# board_sch.net
KiCad netlist of a schematic drawn in EAGLE
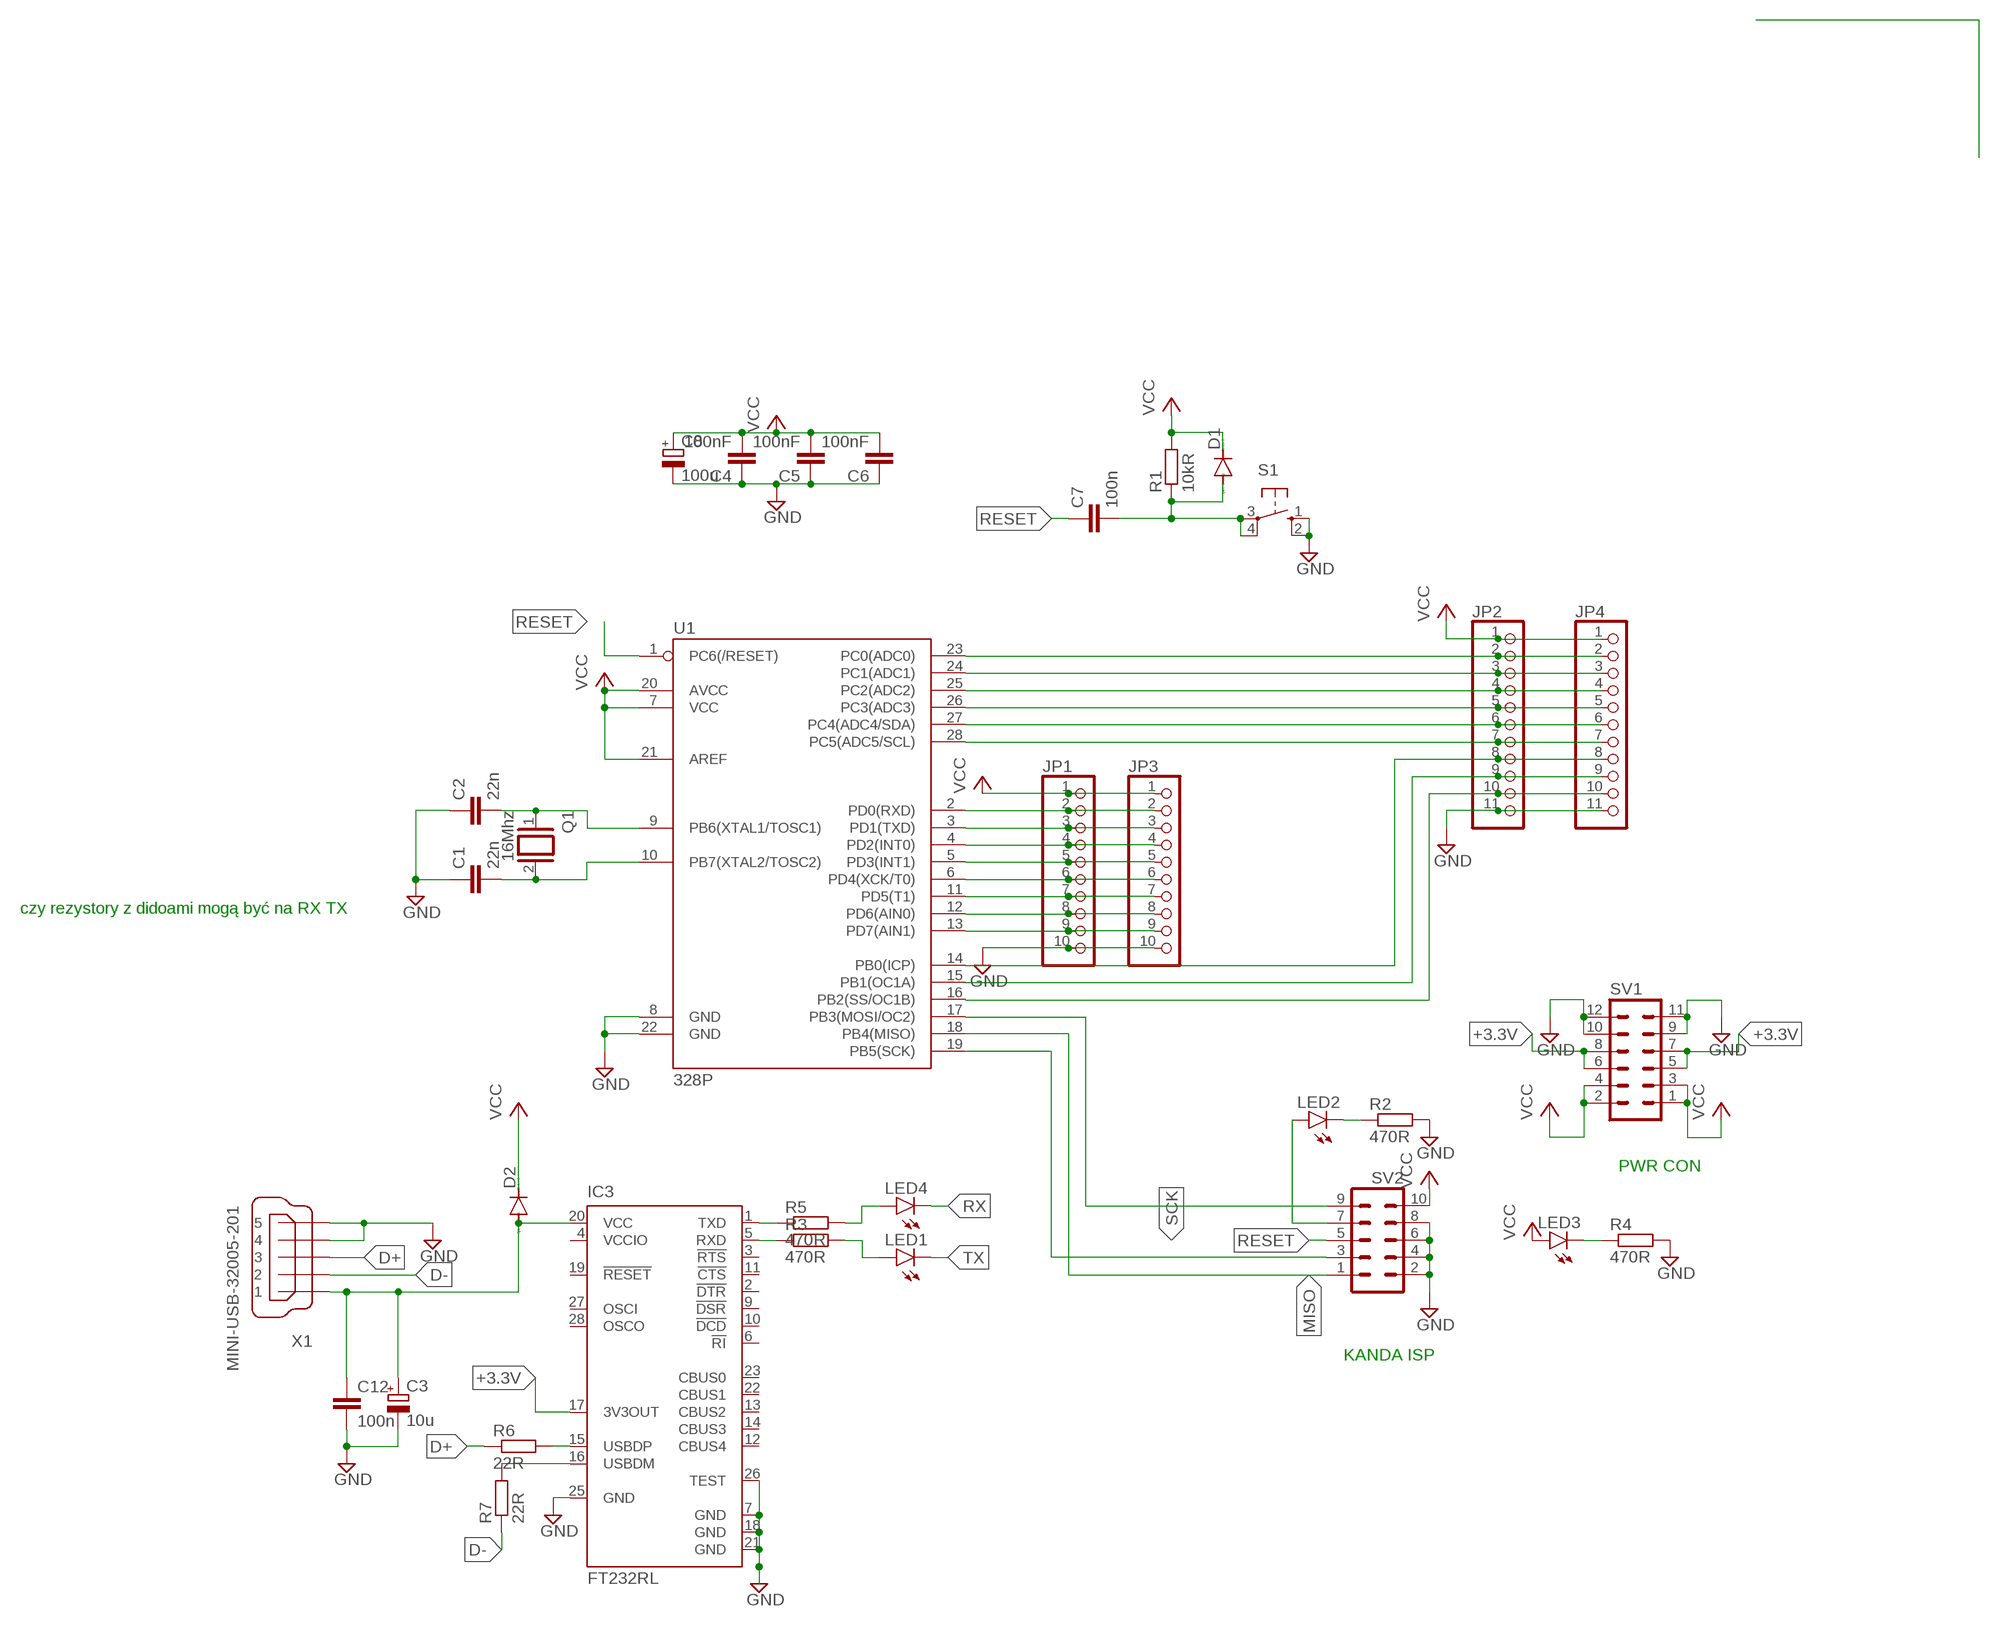
[diagram p0: schematic, sheet 1]

(export (version "E")
  (design (tool "Eeschema 10.0.6"))
  (components
    (comp (ref "C1")
      (value "22n")
      (footprint "eagle-import:C0805")
      (libsource (lib "eagle-import") (part "C-EUC0805"))
    )
    (comp (ref "C2")
      (value "22n")
      (footprint "eagle-import:C0805")
      (libsource (lib "eagle-import") (part "C-EUC0805"))
    )
    (comp (ref "C3")
      (value "10u")
      (footprint "eagle-import:E2,5-6E")
      (libsource (lib "eagle-import") (part "CPOL-EUE2,5-6E"))
    )
    (comp (ref "C4")
      (value "100nF")
      (footprint "eagle-import:C050-025X075")
      (libsource (lib "eagle-import") (part "C-EU050-025X075"))
    )
    (comp (ref "C5")
      (value "100nF")
      (footprint "eagle-import:C050-025X075")
      (libsource (lib "eagle-import") (part "C-EU050-025X075"))
    )
    (comp (ref "C6")
      (value "100nF")
      (footprint "eagle-import:C050-025X075")
      (libsource (lib "eagle-import") (part "C-EU050-025X075"))
    )
    (comp (ref "C7")
      (value "100n")
      (footprint "eagle-import:C0805")
      (libsource (lib "eagle-import") (part "C-EUC0805"))
    )
    (comp (ref "C8")
      (value "100u")
      (footprint "eagle-import:E2,5-6E")
      (libsource (lib "eagle-import") (part "CPOL-EUE2,5-6E"))
    )
    (comp (ref "C12")
      (value "100n")
      (footprint "eagle-import:C0805")
      (libsource (lib "eagle-import") (part "C-EUC0805"))
    )
    (comp (ref "D1")
      (value "DIODE-DO214AC")
      (footprint "eagle-import:DO214AC")
      (libsource (lib "eagle-import") (part "DIODE-DO214AC"))
    )
    (comp (ref "D2")
      (value "DIODE-DO214AC")
      (footprint "eagle-import:DO214AC")
      (libsource (lib "eagle-import") (part "DIODE-DO214AC"))
    )
    (comp (ref "IC3")
      (value "FT232RL")
      (footprint "eagle-import:SSOP28")
      (libsource (lib "eagle-import") (part "FT232RL"))
    )
    (comp (ref "JP1")
      (value "PINHD-1X10")
      (footprint "eagle-import:1X10")
      (libsource (lib "eagle-import") (part "PINHD-1X10"))
    )
    (comp (ref "JP2")
      (value "PINHD-1X11")
      (footprint "eagle-import:1X11")
      (libsource (lib "eagle-import") (part "PINHD-1X11"))
    )
    (comp (ref "JP3")
      (value "PINHD-1X10")
      (footprint "eagle-import:1X10")
      (libsource (lib "eagle-import") (part "PINHD-1X10"))
    )
    (comp (ref "JP4")
      (value "PINHD-1X11")
      (footprint "eagle-import:1X11")
      (libsource (lib "eagle-import") (part "PINHD-1X11"))
    )
    (comp (ref "LED1")
      (value "LEDCHIPLED_0805")
      (footprint "eagle-import:CHIPLED_0805")
      (libsource (lib "eagle-import") (part "LEDCHIPLED_0805"))
    )
    (comp (ref "LED2")
      (value "LEDCHIPLED_0805")
      (footprint "eagle-import:CHIPLED_0805")
      (libsource (lib "eagle-import") (part "LEDCHIPLED_0805"))
    )
    (comp (ref "LED3")
      (value "LEDCHIPLED_0805")
      (footprint "eagle-import:CHIPLED_0805")
      (libsource (lib "eagle-import") (part "LEDCHIPLED_0805"))
    )
    (comp (ref "LED4")
      (value "LEDCHIPLED_0805")
      (footprint "eagle-import:CHIPLED_0805")
      (libsource (lib "eagle-import") (part "LEDCHIPLED_0805"))
    )
    (comp (ref "Q1")
      (value "16Mhz")
      (footprint "eagle-import:QS")
      (libsource (lib "eagle-import") (part "XTAL/S"))
    )
    (comp (ref "R1")
      (value "10kR")
      (footprint "eagle-import:R0805")
      (libsource (lib "eagle-import") (part "R-EU_R0805"))
    )
    (comp (ref "R2")
      (value "470R")
      (footprint "eagle-import:R0805")
      (libsource (lib "eagle-import") (part "R-EU_R0805"))
    )
    (comp (ref "R3")
      (value "470R")
      (footprint "eagle-import:R0805")
      (libsource (lib "eagle-import") (part "R-EU_R0805"))
    )
    (comp (ref "R4")
      (value "470R")
      (footprint "eagle-import:R0805")
      (libsource (lib "eagle-import") (part "R-EU_R0805"))
    )
    (comp (ref "R5")
      (value "470R")
      (footprint "eagle-import:R0805")
      (libsource (lib "eagle-import") (part "R-EU_R0805"))
    )
    (comp (ref "R6")
      (value "22R")
      (footprint "eagle-import:R0805")
      (libsource (lib "eagle-import") (part "R-EU_R0805"))
    )
    (comp (ref "R7")
      (value "22R")
      (footprint "eagle-import:R0805")
      (libsource (lib "eagle-import") (part "R-EU_R0805"))
    )
    (comp (ref "S1")
      (value "10-XX")
      (footprint "eagle-import:B3F-10XX")
      (fields (field (name "MPN") "B3F-1000"))
      (libsource (lib "eagle-import") (part "10-XX"))
    )
    (comp (ref "SV1")
      (value "MA06-2")
      (footprint "eagle-import:MA06-2")
      (libsource (lib "eagle-import") (part "MA06-2"))
    )
    (comp (ref "SV2")
      (value "ML10L")
      (footprint "eagle-import:ML10L")
      (libsource (lib "eagle-import") (part "ML10L"))
    )
    (comp (ref "U1")
      (value "328P")
      (footprint "eagle-import:DIP28")
      (libsource (lib "eagle-import") (part "ATMEGA328P_PDIP"))
    )
    (comp (ref "X1")
      (value "MINI-USB-32005-201")
      (footprint "eagle-import:32005-201")
      (libsource (lib "eagle-import") (part "MINI-USB-32005-201"))
    )
  )
  (nets
    (net (code "1") (name "+3.3V") (class "Default")
      (node (ref "IC3") (pin "17") (pinfunction "3V3OUT_17") (pintype "output"))
      (node (ref "SV1") (pin "5") (pinfunction "5_5") (pintype "passive"))
      (node (ref "SV1") (pin "6") (pinfunction "6_6") (pintype "passive"))
      (node (ref "SV1") (pin "7") (pinfunction "7_7") (pintype "passive"))
      (node (ref "SV1") (pin "8") (pinfunction "8_8") (pintype "passive"))
    )
    (net (code "2") (name "/VCCIO") (class "Default")
      (node (ref "IC3") (pin "4") (pinfunction "VCCIO_4") (pintype "power_in"))
    )
    (net (code "3") (name "D+") (class "Default")
      (node (ref "IC3") (pin "15") (pinfunction "USBDP_15") (pintype "bidirectional"))
      (node (ref "R6") (pin "1") (pinfunction "1_1") (pintype "passive"))
      (node (ref "R6") (pin "2") (pinfunction "2_2") (pintype "passive"))
      (node (ref "X1") (pin "3") (pinfunction "3_3") (pintype "passive"))
    )
    (net (code "4") (name "D-") (class "Default")
      (node (ref "IC3") (pin "16") (pinfunction "USBDM_16") (pintype "bidirectional"))
      (node (ref "R7") (pin "1") (pinfunction "1_1") (pintype "passive"))
      (node (ref "R7") (pin "2") (pinfunction "2_2") (pintype "passive"))
      (node (ref "X1") (pin "2") (pinfunction "2_2") (pintype "passive"))
    )
    (net (code "5") (name "GND") (class "Default")
      (node (ref "C1") (pin "1") (pinfunction "1_1") (pintype "passive"))
      (node (ref "C12") (pin "2") (pinfunction "2_2") (pintype "passive"))
      (node (ref "C2") (pin "1") (pinfunction "1_1") (pintype "passive"))
      (node (ref "C3") (pin "-") (pinfunction "-_-") (pintype "passive"))
      (node (ref "C4") (pin "1") (pinfunction "1_1") (pintype "passive"))
      (node (ref "C5") (pin "1") (pinfunction "1_1") (pintype "passive"))
      (node (ref "C6") (pin "1") (pinfunction "1_1") (pintype "passive"))
      (node (ref "C8") (pin "-") (pinfunction "-_-") (pintype "passive"))
      (node (ref "IC3") (pin "18") (pinfunction "GND_18") (pintype "power_in"))
      (node (ref "IC3") (pin "21") (pinfunction "GND_21") (pintype "power_in"))
      (node (ref "IC3") (pin "25") (pinfunction "GND_25") (pintype "power_in"))
      (node (ref "IC3") (pin "26") (pinfunction "TEST_26") (pintype "input"))
      (node (ref "IC3") (pin "7") (pinfunction "GND_7") (pintype "power_in"))
      (node (ref "JP1") (pin "10") (pinfunction "10_10") (pintype "passive"))
      (node (ref "JP2") (pin "11") (pinfunction "11_11") (pintype "passive"))
      (node (ref "JP3") (pin "10") (pinfunction "10_10") (pintype "passive"))
      (node (ref "JP4") (pin "11") (pinfunction "11_11") (pintype "passive"))
      (node (ref "R2") (pin "2") (pinfunction "2_2") (pintype "passive"))
      (node (ref "R4") (pin "2") (pinfunction "2_2") (pintype "passive"))
      (node (ref "S1") (pin "1") (pinfunction "S_1") (pintype "passive"))
      (node (ref "S1") (pin "2") (pinfunction "S1_2") (pintype "passive"))
      (node (ref "SV1") (pin "10") (pinfunction "10_10") (pintype "passive"))
      (node (ref "SV1") (pin "11") (pinfunction "11_11") (pintype "passive"))
      (node (ref "SV1") (pin "12") (pinfunction "12_12") (pintype "passive"))
      (node (ref "SV1") (pin "9") (pinfunction "9_9") (pintype "passive"))
      (node (ref "SV2") (pin "2") (pinfunction "2_2") (pintype "passive"))
      (node (ref "SV2") (pin "4") (pinfunction "4_4") (pintype "passive"))
      (node (ref "SV2") (pin "6") (pinfunction "6_6") (pintype "passive"))
      (node (ref "SV2") (pin "8") (pinfunction "8_8") (pintype "passive"))
      (node (ref "U1") (pin "22") (pinfunction "GND_22") (pintype "bidirectional"))
      (node (ref "U1") (pin "8") (pinfunction "GND_8") (pintype "bidirectional"))
      (node (ref "X1") (pin "4") (pinfunction "4_4") (pintype "passive"))
      (node (ref "X1") (pin "5") (pinfunction "5_5") (pintype "passive"))
    )
    (net (code "6") (name "MISO") (class "Default")
      (node (ref "SV2") (pin "1") (pinfunction "1_1") (pintype "passive"))
      (node (ref "U1") (pin "18") (pinfunction "PB4(MISO)_18") (pintype "bidirectional"))
    )
    (net (code "7") (name "Net-(IC3-RXD)") (class "Default")
      (node (ref "IC3") (pin "5") (pinfunction "RXD_5") (pintype "input"))
      (node (ref "R3") (pin "1") (pinfunction "1_1") (pintype "passive"))
    )
    (net (code "8") (name "Net-(IC3-TXD)") (class "Default")
      (node (ref "IC3") (pin "1") (pinfunction "TXD_1") (pintype "output"))
      (node (ref "R5") (pin "1") (pinfunction "1_1") (pintype "passive"))
    )
    (net (code "9") (name "Net-(IC3-VCC)") (class "Default")
      (node (ref "C12") (pin "1") (pinfunction "1_1") (pintype "passive"))
      (node (ref "C3") (pin "+") (pinfunction "+_+") (pintype "passive"))
      (node (ref "D2") (pin "A") (pinfunction "A_A") (pintype "passive"))
      (node (ref "IC3") (pin "20") (pinfunction "VCC_20") (pintype "power_in"))
      (node (ref "X1") (pin "1") (pinfunction "1_1") (pintype "passive"))
    )
    (net (code "10") (name "Net-(LED1-PadA)") (class "Default")
      (node (ref "LED1") (pin "A") (pinfunction "A_A") (pintype "passive"))
      (node (ref "R3") (pin "2") (pinfunction "2_2") (pintype "passive"))
    )
    (net (code "11") (name "Net-(LED2-PadA)") (class "Default")
      (node (ref "LED2") (pin "A") (pinfunction "A_A") (pintype "passive"))
      (node (ref "SV2") (pin "7") (pinfunction "7_7") (pintype "passive"))
    )
    (net (code "12") (name "Net-(LED2-PadC)") (class "Default")
      (node (ref "LED2") (pin "C") (pinfunction "C_C") (pintype "passive"))
      (node (ref "R2") (pin "1") (pinfunction "1_1") (pintype "passive"))
    )
    (net (code "13") (name "Net-(LED3-PadC)") (class "Default")
      (node (ref "LED3") (pin "C") (pinfunction "C_C") (pintype "passive"))
      (node (ref "R4") (pin "1") (pinfunction "1_1") (pintype "passive"))
    )
    (net (code "14") (name "Net-(LED4-PadA)") (class "Default")
      (node (ref "LED4") (pin "A") (pinfunction "A_A") (pintype "passive"))
      (node (ref "R5") (pin "2") (pinfunction "2_2") (pintype "passive"))
    )
    (net (code "15") (name "Net-(U1-PB0(ICP))") (class "Default")
      (node (ref "JP2") (pin "8") (pinfunction "8_8") (pintype "passive"))
      (node (ref "JP4") (pin "8") (pinfunction "8_8") (pintype "passive"))
      (node (ref "U1") (pin "14") (pinfunction "PB0(ICP)_14") (pintype "bidirectional"))
    )
    (net (code "16") (name "Net-(U1-PB1(OC1A))") (class "Default")
      (node (ref "JP2") (pin "9") (pinfunction "9_9") (pintype "passive"))
      (node (ref "JP4") (pin "9") (pinfunction "9_9") (pintype "passive"))
      (node (ref "U1") (pin "15") (pinfunction "PB1(OC1A)_15") (pintype "bidirectional"))
    )
    (net (code "17") (name "Net-(U1-PB2(SS{slash}OC1B))") (class "Default")
      (node (ref "JP2") (pin "10") (pinfunction "10_10") (pintype "passive"))
      (node (ref "JP4") (pin "10") (pinfunction "10_10") (pintype "passive"))
      (node (ref "U1") (pin "16") (pinfunction "PB2(SS/OC1B)_16") (pintype "bidirectional"))
    )
    (net (code "18") (name "Net-(U1-PB3(MOSI{slash}OC2))") (class "Default")
      (node (ref "SV2") (pin "9") (pinfunction "9_9") (pintype "passive"))
      (node (ref "U1") (pin "17") (pinfunction "PB3(MOSI/OC2)_17") (pintype "bidirectional"))
    )
    (net (code "19") (name "Net-(U1-PB6(XTAL1{slash}TOSC1))") (class "Default")
      (node (ref "C2") (pin "2") (pinfunction "2_2") (pintype "passive"))
      (node (ref "Q1") (pin "1") (pinfunction "1_1") (pintype "passive"))
      (node (ref "U1") (pin "9") (pinfunction "PB6(XTAL1/TOSC1)_9") (pintype "bidirectional"))
    )
    (net (code "20") (name "Net-(U1-PB7(XTAL2{slash}TOSC2))") (class "Default")
      (node (ref "C1") (pin "2") (pinfunction "2_2") (pintype "passive"))
      (node (ref "Q1") (pin "2") (pinfunction "2_2") (pintype "passive"))
      (node (ref "U1") (pin "10") (pinfunction "PB7(XTAL2/TOSC2)_10") (pintype "bidirectional"))
    )
    (net (code "21") (name "Net-(U1-PC0(ADC0))") (class "Default")
      (node (ref "JP2") (pin "2") (pinfunction "2_2") (pintype "passive"))
      (node (ref "JP4") (pin "2") (pinfunction "2_2") (pintype "passive"))
      (node (ref "U1") (pin "23") (pinfunction "PC0(ADC0)_23") (pintype "bidirectional"))
    )
    (net (code "22") (name "Net-(U1-PC1(ADC1))") (class "Default")
      (node (ref "JP2") (pin "3") (pinfunction "3_3") (pintype "passive"))
      (node (ref "JP4") (pin "3") (pinfunction "3_3") (pintype "passive"))
      (node (ref "U1") (pin "24") (pinfunction "PC1(ADC1)_24") (pintype "bidirectional"))
    )
    (net (code "23") (name "Net-(U1-PC2(ADC2))") (class "Default")
      (node (ref "JP2") (pin "4") (pinfunction "4_4") (pintype "passive"))
      (node (ref "JP4") (pin "4") (pinfunction "4_4") (pintype "passive"))
      (node (ref "U1") (pin "25") (pinfunction "PC2(ADC2)_25") (pintype "bidirectional"))
    )
    (net (code "24") (name "Net-(U1-PC3(ADC3))") (class "Default")
      (node (ref "JP2") (pin "5") (pinfunction "5_5") (pintype "passive"))
      (node (ref "JP4") (pin "5") (pinfunction "5_5") (pintype "passive"))
      (node (ref "U1") (pin "26") (pinfunction "PC3(ADC3)_26") (pintype "bidirectional"))
    )
    (net (code "25") (name "Net-(U1-PC4(ADC4{slash}SDA))") (class "Default")
      (node (ref "JP2") (pin "6") (pinfunction "6_6") (pintype "passive"))
      (node (ref "JP4") (pin "6") (pinfunction "6_6") (pintype "passive"))
      (node (ref "U1") (pin "27") (pinfunction "PC4(ADC4/SDA)_27") (pintype "bidirectional"))
    )
    (net (code "26") (name "Net-(U1-PC5(ADC5{slash}SCL))") (class "Default")
      (node (ref "JP2") (pin "7") (pinfunction "7_7") (pintype "passive"))
      (node (ref "JP4") (pin "7") (pinfunction "7_7") (pintype "passive"))
      (node (ref "U1") (pin "28") (pinfunction "PC5(ADC5/SCL)_28") (pintype "bidirectional"))
    )
    (net (code "27") (name "Net-(U1-PD2(INT0))") (class "Default")
      (node (ref "JP1") (pin "4") (pinfunction "4_4") (pintype "passive"))
      (node (ref "JP3") (pin "4") (pinfunction "4_4") (pintype "passive"))
      (node (ref "U1") (pin "4") (pinfunction "PD2(INT0)_4") (pintype "bidirectional"))
    )
    (net (code "28") (name "Net-(U1-PD3(INT1))") (class "Default")
      (node (ref "JP1") (pin "5") (pinfunction "5_5") (pintype "passive"))
      (node (ref "JP3") (pin "5") (pinfunction "5_5") (pintype "passive"))
      (node (ref "U1") (pin "5") (pinfunction "PD3(INT1)_5") (pintype "bidirectional"))
    )
    (net (code "29") (name "Net-(U1-PD4(XCK{slash}T0))") (class "Default")
      (node (ref "JP1") (pin "6") (pinfunction "6_6") (pintype "passive"))
      (node (ref "JP3") (pin "6") (pinfunction "6_6") (pintype "passive"))
      (node (ref "U1") (pin "6") (pinfunction "PD4(XCK/T0)_6") (pintype "bidirectional"))
    )
    (net (code "30") (name "Net-(U1-PD5(T1))") (class "Default")
      (node (ref "JP1") (pin "7") (pinfunction "7_7") (pintype "passive"))
      (node (ref "JP3") (pin "7") (pinfunction "7_7") (pintype "passive"))
      (node (ref "U1") (pin "11") (pinfunction "PD5(T1)_11") (pintype "bidirectional"))
    )
    (net (code "31") (name "Net-(U1-PD6(AIN0))") (class "Default")
      (node (ref "JP1") (pin "8") (pinfunction "8_8") (pintype "passive"))
      (node (ref "JP3") (pin "8") (pinfunction "8_8") (pintype "passive"))
      (node (ref "U1") (pin "12") (pinfunction "PD6(AIN0)_12") (pintype "bidirectional"))
    )
    (net (code "32") (name "Net-(U1-PD7(AIN1))") (class "Default")
      (node (ref "JP1") (pin "9") (pinfunction "9_9") (pintype "passive"))
      (node (ref "JP3") (pin "9") (pinfunction "9_9") (pintype "passive"))
      (node (ref "U1") (pin "13") (pinfunction "PD7(AIN1)_13") (pintype "bidirectional"))
    )
    (net (code "33") (name "RESET") (class "Default")
      (node (ref "C7") (pin "1") (pinfunction "1_1") (pintype "passive"))
      (node (ref "C7") (pin "2") (pinfunction "2_2") (pintype "passive"))
      (node (ref "D1") (pin "A") (pinfunction "A_A") (pintype "passive"))
      (node (ref "R1") (pin "1") (pinfunction "1_1") (pintype "passive"))
      (node (ref "S1") (pin "3") (pinfunction "P_3") (pintype "passive"))
      (node (ref "S1") (pin "4") (pinfunction "P1_4") (pintype "passive"))
      (node (ref "SV2") (pin "5") (pinfunction "5_5") (pintype "passive"))
      (node (ref "U1") (pin "1") (pinfunction "PC6(/RESET)_1") (pintype "bidirectional"))
    )
    (net (code "34") (name "RX") (class "Default")
      (node (ref "JP1") (pin "2") (pinfunction "2_2") (pintype "passive"))
      (node (ref "JP3") (pin "2") (pinfunction "2_2") (pintype "passive"))
      (node (ref "LED4") (pin "C") (pinfunction "C_C") (pintype "passive"))
      (node (ref "U1") (pin "2") (pinfunction "PD0(RXD)_2") (pintype "bidirectional"))
    )
    (net (code "35") (name "SCK") (class "Default")
      (node (ref "SV2") (pin "3") (pinfunction "3_3") (pintype "passive"))
      (node (ref "U1") (pin "19") (pinfunction "PB5(SCK)_19") (pintype "bidirectional"))
    )
    (net (code "36") (name "TX") (class "Default")
      (node (ref "JP1") (pin "3") (pinfunction "3_3") (pintype "passive"))
      (node (ref "JP3") (pin "3") (pinfunction "3_3") (pintype "passive"))
      (node (ref "LED1") (pin "C") (pinfunction "C_C") (pintype "passive"))
      (node (ref "U1") (pin "3") (pinfunction "PD1(TXD)_3") (pintype "bidirectional"))
    )
    (net (code "37") (name "VCC") (class "Default")
      (node (ref "C4") (pin "2") (pinfunction "2_2") (pintype "passive"))
      (node (ref "C5") (pin "2") (pinfunction "2_2") (pintype "passive"))
      (node (ref "C6") (pin "2") (pinfunction "2_2") (pintype "passive"))
      (node (ref "C8") (pin "+") (pinfunction "+_+") (pintype "passive"))
      (node (ref "D1") (pin "C") (pinfunction "C_C") (pintype "passive"))
      (node (ref "D2") (pin "C") (pinfunction "C_C") (pintype "passive"))
      (node (ref "JP1") (pin "1") (pinfunction "1_1") (pintype "passive"))
      (node (ref "JP2") (pin "1") (pinfunction "1_1") (pintype "passive"))
      (node (ref "JP3") (pin "1") (pinfunction "1_1") (pintype "passive"))
      (node (ref "JP4") (pin "1") (pinfunction "1_1") (pintype "passive"))
      (node (ref "LED3") (pin "A") (pinfunction "A_A") (pintype "passive"))
      (node (ref "R1") (pin "2") (pinfunction "2_2") (pintype "passive"))
      (node (ref "SV1") (pin "1") (pinfunction "1_1") (pintype "passive"))
      (node (ref "SV1") (pin "2") (pinfunction "2_2") (pintype "passive"))
      (node (ref "SV1") (pin "3") (pinfunction "3_3") (pintype "passive"))
      (node (ref "SV1") (pin "4") (pinfunction "4_4") (pintype "passive"))
      (node (ref "SV2") (pin "10") (pinfunction "10_10") (pintype "passive"))
      (node (ref "U1") (pin "20") (pinfunction "AVCC_20") (pintype "bidirectional"))
      (node (ref "U1") (pin "21") (pinfunction "AREF_21") (pintype "bidirectional"))
      (node (ref "U1") (pin "7") (pinfunction "VCC_7") (pintype "bidirectional"))
    )
    (net (code "38") (name "unconnected-(IC3-CBUS0-Pad23)") (class "Default")
      (node (ref "IC3") (pin "23") (pinfunction "CBUS0_23") (pintype "bidirectional"))
    )
    (net (code "39") (name "unconnected-(IC3-CBUS1-Pad22)") (class "Default")
      (node (ref "IC3") (pin "22") (pinfunction "CBUS1_22") (pintype "bidirectional"))
    )
    (net (code "40") (name "unconnected-(IC3-CBUS2-Pad13)") (class "Default")
      (node (ref "IC3") (pin "13") (pinfunction "CBUS2_13") (pintype "bidirectional"))
    )
    (net (code "41") (name "unconnected-(IC3-CBUS3-Pad14)") (class "Default")
      (node (ref "IC3") (pin "14") (pinfunction "CBUS3_14") (pintype "bidirectional"))
    )
    (net (code "42") (name "unconnected-(IC3-CBUS4-Pad12)") (class "Default")
      (node (ref "IC3") (pin "12") (pinfunction "CBUS4_12") (pintype "bidirectional"))
    )
    (net (code "43") (name "unconnected-(IC3-OSCI-Pad27)") (class "Default")
      (node (ref "IC3") (pin "27") (pinfunction "OSCI_27") (pintype "input"))
    )
    (net (code "44") (name "unconnected-(IC3-OSCO-Pad28)") (class "Default")
      (node (ref "IC3") (pin "28") (pinfunction "OSCO_28") (pintype "output"))
    )
    (net (code "45") (name "unconnected-(IC3-~{CTS}-Pad11)") (class "Default")
      (node (ref "IC3") (pin "11") (pinfunction "~{CTS}_11") (pintype "input"))
    )
    (net (code "46") (name "unconnected-(IC3-~{DCD}-Pad10)") (class "Default")
      (node (ref "IC3") (pin "10") (pinfunction "~{DCD}_10") (pintype "input"))
    )
    (net (code "47") (name "unconnected-(IC3-~{DSR}-Pad9)") (class "Default")
      (node (ref "IC3") (pin "9") (pinfunction "~{DSR}_9") (pintype "input"))
    )
    (net (code "48") (name "unconnected-(IC3-~{DTR}-Pad2)") (class "Default")
      (node (ref "IC3") (pin "2") (pinfunction "~{DTR}_2") (pintype "output"))
    )
    (net (code "49") (name "unconnected-(IC3-~{RESET}-Pad19)") (class "Default")
      (node (ref "IC3") (pin "19") (pinfunction "~{RESET}_19") (pintype "input"))
    )
    (net (code "50") (name "unconnected-(IC3-~{RI}-Pad6)") (class "Default")
      (node (ref "IC3") (pin "6") (pinfunction "~{RI}_6") (pintype "input"))
    )
    (net (code "51") (name "unconnected-(IC3-~{RTS}-Pad3)") (class "Default")
      (node (ref "IC3") (pin "3") (pinfunction "~{RTS}_3") (pintype "output"))
    )
  )
)
